# top.net
KiCad netlist of a schematic drawn in Altium Designer
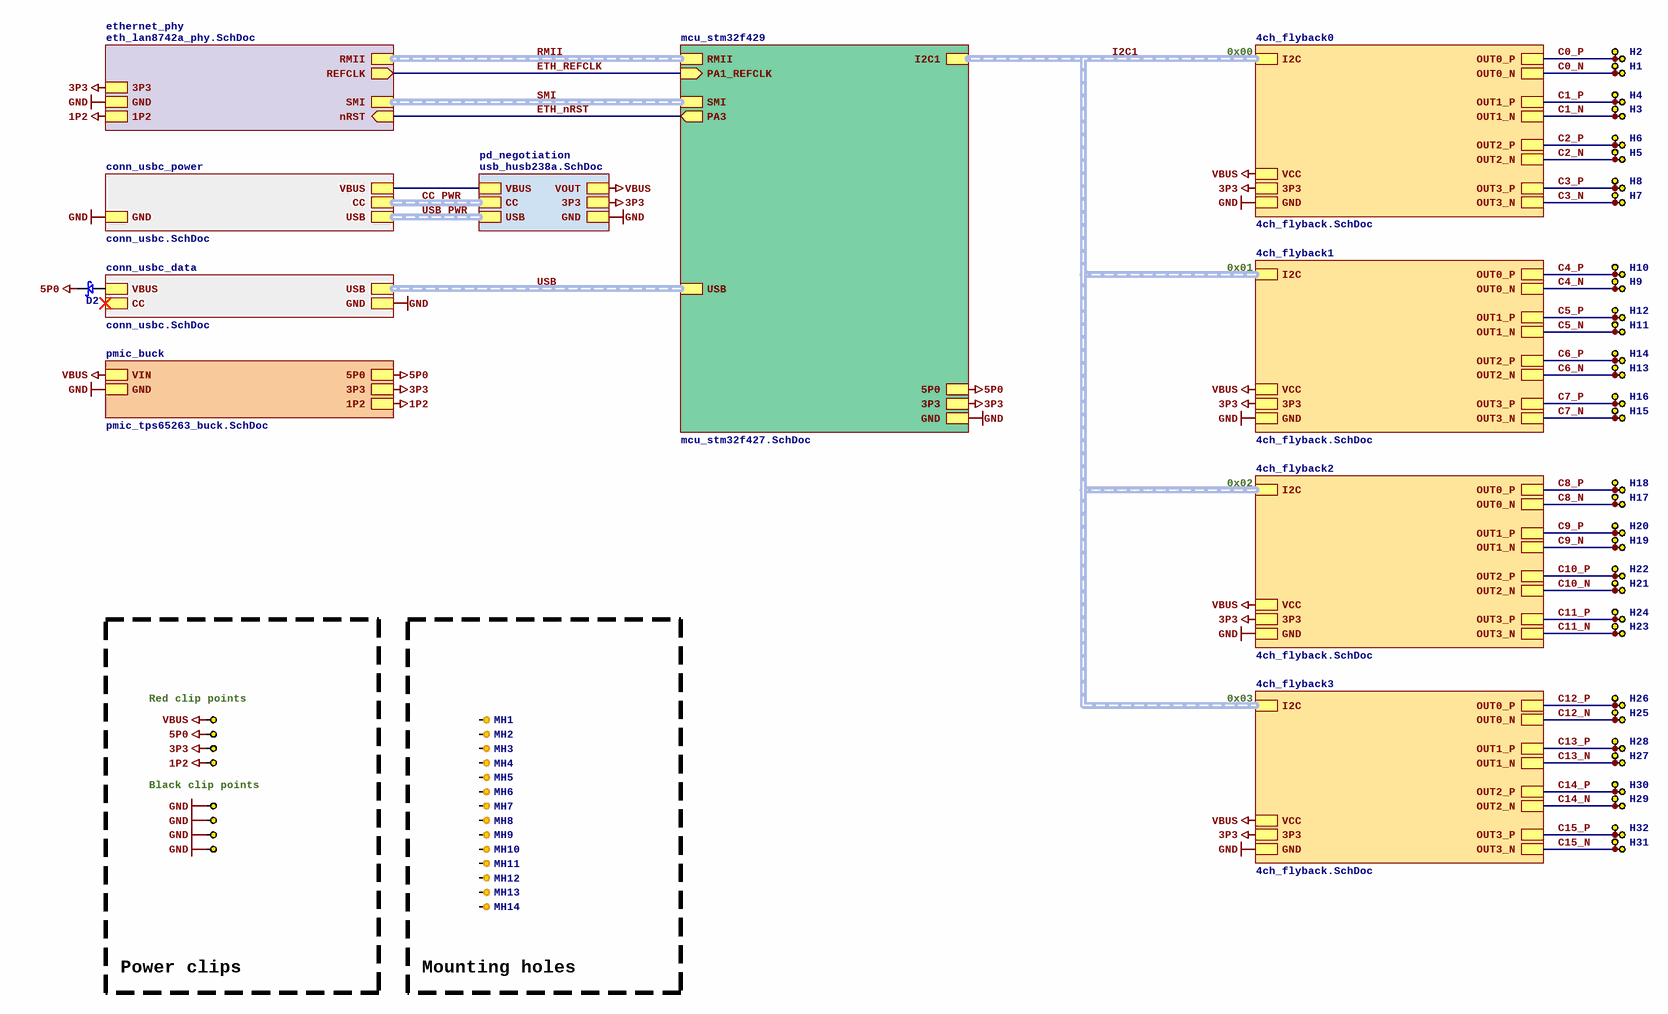
[diagram p0: top.SchDoc]

(export (version "E")
  (design (tool "Eeschema 10.0.6"))
  (components
    (comp (ref "D2")
      (value "B340A-13-F")
      (footprint "SMA")
      (description "Rectifier Diode, Schottky, 1 Phase, 1 Element, 3A, 40V V(RRM), Silicon")
      (fields (field (name "MANUFACTURER") "Diodes"))
      (libsource (lib "SSCP") (part "SCHOTTKY_B340A-13-F"))
    )
    (comp (ref "H1")
      (value "SMTSO-M2-10ET")
      (footprint "SMTSO-M2-10ET")
      (libsource (lib "SSCP") (part "STANDOFF_SMTSO-M2-10ET"))
    )
    (comp (ref "H2")
      (value "SMTSO-M2-10ET")
      (footprint "SMTSO-M2-10ET")
      (libsource (lib "SSCP") (part "STANDOFF_SMTSO-M2-10ET"))
    )
    (comp (ref "H3")
      (value "SMTSO-M2-10ET")
      (footprint "SMTSO-M2-10ET")
      (libsource (lib "SSCP") (part "STANDOFF_SMTSO-M2-10ET"))
    )
    (comp (ref "H4")
      (value "SMTSO-M2-10ET")
      (footprint "SMTSO-M2-10ET")
      (libsource (lib "SSCP") (part "STANDOFF_SMTSO-M2-10ET"))
    )
    (comp (ref "H5")
      (value "SMTSO-M2-10ET")
      (footprint "SMTSO-M2-10ET")
      (libsource (lib "SSCP") (part "STANDOFF_SMTSO-M2-10ET"))
    )
    (comp (ref "H6")
      (value "SMTSO-M2-10ET")
      (footprint "SMTSO-M2-10ET")
      (libsource (lib "SSCP") (part "STANDOFF_SMTSO-M2-10ET"))
    )
    (comp (ref "H7")
      (value "SMTSO-M2-10ET")
      (footprint "SMTSO-M2-10ET")
      (libsource (lib "SSCP") (part "STANDOFF_SMTSO-M2-10ET"))
    )
    (comp (ref "H8")
      (value "SMTSO-M2-10ET")
      (footprint "SMTSO-M2-10ET")
      (libsource (lib "SSCP") (part "STANDOFF_SMTSO-M2-10ET"))
    )
    (comp (ref "H9")
      (value "SMTSO-M2-10ET")
      (footprint "SMTSO-M2-10ET")
      (libsource (lib "SSCP") (part "STANDOFF_SMTSO-M2-10ET"))
    )
    (comp (ref "H10")
      (value "SMTSO-M2-10ET")
      (footprint "SMTSO-M2-10ET")
      (libsource (lib "SSCP") (part "STANDOFF_SMTSO-M2-10ET"))
    )
    (comp (ref "H11")
      (value "SMTSO-M2-10ET")
      (footprint "SMTSO-M2-10ET")
      (libsource (lib "SSCP") (part "STANDOFF_SMTSO-M2-10ET"))
    )
    (comp (ref "H12")
      (value "SMTSO-M2-10ET")
      (footprint "SMTSO-M2-10ET")
      (libsource (lib "SSCP") (part "STANDOFF_SMTSO-M2-10ET"))
    )
    (comp (ref "H13")
      (value "SMTSO-M2-10ET")
      (footprint "SMTSO-M2-10ET")
      (libsource (lib "SSCP") (part "STANDOFF_SMTSO-M2-10ET"))
    )
    (comp (ref "H14")
      (value "SMTSO-M2-10ET")
      (footprint "SMTSO-M2-10ET")
      (libsource (lib "SSCP") (part "STANDOFF_SMTSO-M2-10ET"))
    )
    (comp (ref "H15")
      (value "SMTSO-M2-10ET")
      (footprint "SMTSO-M2-10ET")
      (libsource (lib "SSCP") (part "STANDOFF_SMTSO-M2-10ET"))
    )
    (comp (ref "H16")
      (value "SMTSO-M2-10ET")
      (footprint "SMTSO-M2-10ET")
      (libsource (lib "SSCP") (part "STANDOFF_SMTSO-M2-10ET"))
    )
    (comp (ref "H17")
      (value "SMTSO-M2-10ET")
      (footprint "SMTSO-M2-10ET")
      (libsource (lib "SSCP") (part "STANDOFF_SMTSO-M2-10ET"))
    )
    (comp (ref "H18")
      (value "SMTSO-M2-10ET")
      (footprint "SMTSO-M2-10ET")
      (libsource (lib "SSCP") (part "STANDOFF_SMTSO-M2-10ET"))
    )
    (comp (ref "H19")
      (value "SMTSO-M2-10ET")
      (footprint "SMTSO-M2-10ET")
      (libsource (lib "SSCP") (part "STANDOFF_SMTSO-M2-10ET"))
    )
    (comp (ref "H20")
      (value "SMTSO-M2-10ET")
      (footprint "SMTSO-M2-10ET")
      (libsource (lib "SSCP") (part "STANDOFF_SMTSO-M2-10ET"))
    )
    (comp (ref "H21")
      (value "SMTSO-M2-10ET")
      (footprint "SMTSO-M2-10ET")
      (libsource (lib "SSCP") (part "STANDOFF_SMTSO-M2-10ET"))
    )
    (comp (ref "H22")
      (value "SMTSO-M2-10ET")
      (footprint "SMTSO-M2-10ET")
      (libsource (lib "SSCP") (part "STANDOFF_SMTSO-M2-10ET"))
    )
    (comp (ref "H23")
      (value "SMTSO-M2-10ET")
      (footprint "SMTSO-M2-10ET")
      (libsource (lib "SSCP") (part "STANDOFF_SMTSO-M2-10ET"))
    )
    (comp (ref "H24")
      (value "SMTSO-M2-10ET")
      (footprint "SMTSO-M2-10ET")
      (libsource (lib "SSCP") (part "STANDOFF_SMTSO-M2-10ET"))
    )
    (comp (ref "H25")
      (value "SMTSO-M2-10ET")
      (footprint "SMTSO-M2-10ET")
      (libsource (lib "SSCP") (part "STANDOFF_SMTSO-M2-10ET"))
    )
    (comp (ref "H26")
      (value "SMTSO-M2-10ET")
      (footprint "SMTSO-M2-10ET")
      (libsource (lib "SSCP") (part "STANDOFF_SMTSO-M2-10ET"))
    )
    (comp (ref "H27")
      (value "SMTSO-M2-10ET")
      (footprint "SMTSO-M2-10ET")
      (libsource (lib "SSCP") (part "STANDOFF_SMTSO-M2-10ET"))
    )
    (comp (ref "H28")
      (value "SMTSO-M2-10ET")
      (footprint "SMTSO-M2-10ET")
      (libsource (lib "SSCP") (part "STANDOFF_SMTSO-M2-10ET"))
    )
    (comp (ref "H29")
      (value "SMTSO-M2-10ET")
      (footprint "SMTSO-M2-10ET")
      (libsource (lib "SSCP") (part "STANDOFF_SMTSO-M2-10ET"))
    )
    (comp (ref "H30")
      (value "SMTSO-M2-10ET")
      (footprint "SMTSO-M2-10ET")
      (libsource (lib "SSCP") (part "STANDOFF_SMTSO-M2-10ET"))
    )
    (comp (ref "H31")
      (value "SMTSO-M2-10ET")
      (footprint "SMTSO-M2-10ET")
      (libsource (lib "SSCP") (part "STANDOFF_SMTSO-M2-10ET"))
    )
    (comp (ref "H32")
      (value "SMTSO-M2-10ET")
      (footprint "SMTSO-M2-10ET")
      (libsource (lib "SSCP") (part "STANDOFF_SMTSO-M2-10ET"))
    )
    (comp (ref "MH1") (value "HOLE") (footprint "HOLE_M3") (libsource (lib "miscellaneous") (part "HOLE")))
    (comp (ref "MH2") (value "HOLE") (footprint "HOLE_M3") (libsource (lib "miscellaneous") (part "HOLE")))
    (comp (ref "MH3") (value "HOLE") (footprint "HOLE_M3") (libsource (lib "miscellaneous") (part "HOLE")))
    (comp (ref "MH4") (value "HOLE") (footprint "HOLE_M3") (libsource (lib "miscellaneous") (part "HOLE")))
    (comp (ref "MH5") (value "HOLE") (footprint "HOLE_M3") (libsource (lib "miscellaneous") (part "HOLE")))
    (comp (ref "MH6") (value "HOLE") (footprint "HOLE_M3") (libsource (lib "miscellaneous") (part "HOLE")))
    (comp (ref "MH7") (value "HOLE") (footprint "HOLE_M3") (libsource (lib "miscellaneous") (part "HOLE")))
    (comp (ref "MH8") (value "HOLE") (footprint "HOLE_M3") (libsource (lib "miscellaneous") (part "HOLE")))
    (comp (ref "MH9") (value "HOLE") (footprint "HOLE_M3") (libsource (lib "miscellaneous") (part "HOLE")))
    (comp (ref "MH10") (value "HOLE") (footprint "HOLE_M3") (libsource (lib "miscellaneous") (part "HOLE")))
    (comp (ref "MH11") (value "HOLE") (footprint "HOLE_M3") (libsource (lib "miscellaneous") (part "HOLE")))
    (comp (ref "MH12") (value "HOLE") (footprint "HOLE_M3") (libsource (lib "miscellaneous") (part "HOLE")))
    (comp (ref "MH13") (value "HOLE") (footprint "HOLE_M3") (libsource (lib "miscellaneous") (part "HOLE")))
    (comp (ref "MH14") (value "HOLE") (footprint "HOLE_M3") (libsource (lib "miscellaneous") (part "HOLE")))
    (comp (ref "TP3")
      (value "RH-5000")
      (footprint "TP_RH-5000")
      (fields (field (name "MANUFACTURER") "ronghe"))
      (libsource (lib "database") (part "__template_testpoint"))
    )
    (comp (ref "TP4")
      (value "RH-5000")
      (footprint "TP_RH-5000")
      (fields (field (name "MANUFACTURER") "ronghe"))
      (libsource (lib "database") (part "__template_testpoint"))
    )
    (comp (ref "TP5")
      (value "RH-5001")
      (footprint "TP_RH-5001")
      (fields (field (name "MANUFACTURER") "ronghe"))
      (libsource (lib "database") (part "__template_testpoint"))
    )
    (comp (ref "TP6")
      (value "RH-5000")
      (footprint "TP_RH-5000")
      (fields (field (name "MANUFACTURER") "ronghe"))
      (libsource (lib "database") (part "__template_testpoint"))
    )
    (comp (ref "TP7")
      (value "RH-5001")
      (footprint "TP_RH-5001")
      (fields (field (name "MANUFACTURER") "ronghe"))
      (libsource (lib "database") (part "__template_testpoint"))
    )
    (comp (ref "TP8")
      (value "RH-5000")
      (footprint "TP_RH-5000")
      (fields (field (name "MANUFACTURER") "ronghe"))
      (libsource (lib "database") (part "__template_testpoint"))
    )
    (comp (ref "TP9")
      (value "RH-5001")
      (footprint "TP_RH-5001")
      (fields (field (name "MANUFACTURER") "ronghe"))
      (libsource (lib "database") (part "__template_testpoint"))
    )
    (comp (ref "TP10")
      (value "RH-5000")
      (footprint "TP_RH-5000")
      (fields (field (name "MANUFACTURER") "ronghe"))
      (libsource (lib "database") (part "__template_testpoint"))
    )
    (comp (ref "TP11")
      (value "RH-5001")
      (footprint "TP_RH-5001")
      (fields (field (name "MANUFACTURER") "ronghe"))
      (libsource (lib "database") (part "__template_testpoint"))
    )
    (comp (ref "TP12")
      (value "RH-5000")
      (footprint "TP_RH-5000")
      (fields (field (name "MANUFACTURER") "ronghe"))
      (libsource (lib "database") (part "__template_testpoint"))
    )
    (comp (ref "TP13")
      (value "RH-5001")
      (footprint "TP_RH-5001")
      (fields (field (name "MANUFACTURER") "ronghe"))
      (libsource (lib "database") (part "__template_testpoint"))
    )
    (comp (ref "TP14")
      (value "RH-5000")
      (footprint "TP_RH-5000")
      (fields (field (name "MANUFACTURER") "ronghe"))
      (libsource (lib "database") (part "__template_testpoint"))
    )
    (comp (ref "TP15")
      (value "RH-5001")
      (footprint "TP_RH-5001")
      (fields (field (name "MANUFACTURER") "ronghe"))
      (libsource (lib "database") (part "__template_testpoint"))
    )
    (comp (ref "TP16")
      (value "RH-5000")
      (footprint "TP_RH-5000")
      (fields (field (name "MANUFACTURER") "ronghe"))
      (libsource (lib "database") (part "__template_testpoint"))
    )
    (comp (ref "TP17")
      (value "RH-5001")
      (footprint "TP_RH-5001")
      (fields (field (name "MANUFACTURER") "ronghe"))
      (libsource (lib "database") (part "__template_testpoint"))
    )
    (comp (ref "TP18")
      (value "RH-5000")
      (footprint "TP_RH-5000")
      (fields (field (name "MANUFACTURER") "ronghe"))
      (libsource (lib "database") (part "__template_testpoint"))
    )
    (comp (ref "TP19")
      (value "RH-5001")
      (footprint "TP_RH-5001")
      (fields (field (name "MANUFACTURER") "ronghe"))
      (libsource (lib "database") (part "__template_testpoint"))
    )
    (comp (ref "TP20")
      (value "RH-5000")
      (footprint "TP_RH-5000")
      (fields (field (name "MANUFACTURER") "ronghe"))
      (libsource (lib "database") (part "__template_testpoint"))
    )
    (comp (ref "TP21")
      (value "RH-5001")
      (footprint "TP_RH-5001")
      (fields (field (name "MANUFACTURER") "ronghe"))
      (libsource (lib "database") (part "__template_testpoint"))
    )
    (comp (ref "TP22")
      (value "RH-5000")
      (footprint "TP_RH-5000")
      (fields (field (name "MANUFACTURER") "ronghe"))
      (libsource (lib "database") (part "__template_testpoint"))
    )
    (comp (ref "TP23")
      (value "RH-5001")
      (footprint "TP_RH-5001")
      (fields (field (name "MANUFACTURER") "ronghe"))
      (libsource (lib "database") (part "__template_testpoint"))
    )
    (comp (ref "TP24")
      (value "RH-5000")
      (footprint "TP_RH-5000")
      (fields (field (name "MANUFACTURER") "ronghe"))
      (libsource (lib "database") (part "__template_testpoint"))
    )
    (comp (ref "TP25")
      (value "RH-5001")
      (footprint "TP_RH-5001")
      (fields (field (name "MANUFACTURER") "ronghe"))
      (libsource (lib "database") (part "__template_testpoint"))
    )
    (comp (ref "TP26")
      (value "RH-5000")
      (footprint "TP_RH-5000")
      (fields (field (name "MANUFACTURER") "ronghe"))
      (libsource (lib "database") (part "__template_testpoint"))
    )
    (comp (ref "TP27")
      (value "RH-5001")
      (footprint "TP_RH-5001")
      (fields (field (name "MANUFACTURER") "ronghe"))
      (libsource (lib "database") (part "__template_testpoint"))
    )
    (comp (ref "TP28")
      (value "RH-5000")
      (footprint "TP_RH-5000")
      (fields (field (name "MANUFACTURER") "ronghe"))
      (libsource (lib "database") (part "__template_testpoint"))
    )
    (comp (ref "TP29")
      (value "RH-5001")
      (footprint "TP_RH-5001")
      (fields (field (name "MANUFACTURER") "ronghe"))
      (libsource (lib "database") (part "__template_testpoint"))
    )
    (comp (ref "TP30")
      (value "RH-5000")
      (footprint "TP_RH-5000")
      (fields (field (name "MANUFACTURER") "ronghe"))
      (libsource (lib "database") (part "__template_testpoint"))
    )
    (comp (ref "TP31")
      (value "RH-5001")
      (footprint "TP_RH-5001")
      (fields (field (name "MANUFACTURER") "ronghe"))
      (libsource (lib "database") (part "__template_testpoint"))
    )
    (comp (ref "TP32")
      (value "RH-5000")
      (footprint "TP_RH-5000")
      (fields (field (name "MANUFACTURER") "ronghe"))
      (libsource (lib "database") (part "__template_testpoint"))
    )
    (comp (ref "TP33")
      (value "RH-5000")
      (footprint "TP_RH-5000")
      (fields (field (name "MANUFACTURER") "ronghe"))
      (libsource (lib "database") (part "__template_testpoint"))
    )
    (comp (ref "TP34")
      (value "RH-5001")
      (footprint "TP_RH-5001")
      (fields (field (name "MANUFACTURER") "ronghe"))
      (libsource (lib "database") (part "__template_testpoint"))
    )
    (comp (ref "TP35")
      (value "RH-5000")
      (footprint "TP_RH-5000")
      (fields (field (name "MANUFACTURER") "ronghe"))
      (libsource (lib "database") (part "__template_testpoint"))
    )
    (comp (ref "TP36")
      (value "RH-5000")
      (footprint "TP_RH-5000")
      (fields (field (name "MANUFACTURER") "ronghe"))
      (libsource (lib "database") (part "__template_testpoint"))
    )
    (comp (ref "TP37")
      (value "RH-5000")
      (footprint "TP_RH-5000")
      (fields (field (name "MANUFACTURER") "ronghe"))
      (libsource (lib "database") (part "__template_testpoint"))
    )
    (comp (ref "TP38")
      (value "RH-5001")
      (footprint "TP_RH-5001")
      (fields (field (name "MANUFACTURER") "ronghe"))
      (libsource (lib "database") (part "__template_testpoint"))
    )
    (comp (ref "TP39")
      (value "RH-5001")
      (footprint "TP_RH-5001")
      (fields (field (name "MANUFACTURER") "ronghe"))
      (libsource (lib "database") (part "__template_testpoint"))
    )
    (comp (ref "TP41")
      (value "RH-5001")
      (footprint "TP_RH-5001")
      (fields (field (name "MANUFACTURER") "ronghe"))
      (libsource (lib "database") (part "__template_testpoint"))
    )
    (comp (ref "TP43")
      (value "RH-5001")
      (footprint "TP_RH-5001")
      (fields (field (name "MANUFACTURER") "ronghe"))
      (libsource (lib "database") (part "__template_testpoint"))
    )
    (comp (ref "TP45")
      (value "RH-5001")
      (footprint "TP_RH-5001")
      (fields (field (name "MANUFACTURER") "ronghe"))
      (libsource (lib "database") (part "__template_testpoint"))
    )
  )
  (nets
    (net (code "7") (name "/C0_N") (class "Default")
      (node (ref "H1") (pin "1") (pintype "passive"))
      (node (ref "TP5") (pin "1") (pintype "passive"))
    )
    (net (code "8") (name "/C0_P") (class "Default")
      (node (ref "H2") (pin "1") (pintype "passive"))
      (node (ref "TP4") (pin "1") (pintype "passive"))
    )
    (net (code "9") (name "/C1_N") (class "Default")
      (node (ref "H3") (pin "1") (pintype "passive"))
      (node (ref "TP7") (pin "1") (pintype "passive"))
    )
    (net (code "10") (name "/C1_P") (class "Default")
      (node (ref "H4") (pin "1") (pintype "passive"))
      (node (ref "TP6") (pin "1") (pintype "passive"))
    )
    (net (code "11") (name "/C2_N") (class "Default")
      (node (ref "H5") (pin "1") (pintype "passive"))
      (node (ref "TP9") (pin "1") (pintype "passive"))
    )
    (net (code "12") (name "/C2_P") (class "Default")
      (node (ref "H6") (pin "1") (pintype "passive"))
      (node (ref "TP8") (pin "1") (pintype "passive"))
    )
    (net (code "13") (name "/C3_N") (class "Default")
      (node (ref "H7") (pin "1") (pintype "passive"))
      (node (ref "TP11") (pin "1") (pintype "passive"))
    )
    (net (code "14") (name "/C3_P") (class "Default")
      (node (ref "H8") (pin "1") (pintype "passive"))
      (node (ref "TP10") (pin "1") (pintype "passive"))
    )
    (net (code "15") (name "/C4_N") (class "Default")
      (node (ref "H9") (pin "1") (pintype "passive"))
      (node (ref "TP13") (pin "1") (pintype "passive"))
    )
    (net (code "16") (name "/C4_P") (class "Default")
      (node (ref "H10") (pin "1") (pintype "passive"))
      (node (ref "TP12") (pin "1") (pintype "passive"))
    )
    (net (code "17") (name "/C5_N") (class "Default")
      (node (ref "H11") (pin "1") (pintype "passive"))
      (node (ref "TP15") (pin "1") (pintype "passive"))
    )
    (net (code "18") (name "/C5_P") (class "Default")
      (node (ref "H12") (pin "1") (pintype "passive"))
      (node (ref "TP14") (pin "1") (pintype "passive"))
    )
    (net (code "19") (name "/C6_N") (class "Default")
      (node (ref "H13") (pin "1") (pintype "passive"))
      (node (ref "TP17") (pin "1") (pintype "passive"))
    )
    (net (code "20") (name "/C6_P") (class "Default")
      (node (ref "H14") (pin "1") (pintype "passive"))
      (node (ref "TP16") (pin "1") (pintype "passive"))
    )
    (net (code "21") (name "/C7_N") (class "Default")
      (node (ref "H15") (pin "1") (pintype "passive"))
      (node (ref "TP19") (pin "1") (pintype "passive"))
    )
    (net (code "22") (name "/C7_P") (class "Default")
      (node (ref "H16") (pin "1") (pintype "passive"))
      (node (ref "TP18") (pin "1") (pintype "passive"))
    )
    (net (code "23") (name "/C8_N") (class "Default")
      (node (ref "H17") (pin "1") (pintype "passive"))
      (node (ref "TP21") (pin "1") (pintype "passive"))
    )
    (net (code "24") (name "/C8_P") (class "Default")
      (node (ref "H18") (pin "1") (pintype "passive"))
      (node (ref "TP20") (pin "1") (pintype "passive"))
    )
    (net (code "25") (name "/C9_N") (class "Default")
      (node (ref "H19") (pin "1") (pintype "passive"))
      (node (ref "TP23") (pin "1") (pintype "passive"))
    )
    (net (code "26") (name "/C9_P") (class "Default")
      (node (ref "H20") (pin "1") (pintype "passive"))
      (node (ref "TP22") (pin "1") (pintype "passive"))
    )
    (net (code "27") (name "/C10_N") (class "Default")
      (node (ref "H21") (pin "1") (pintype "passive"))
      (node (ref "TP25") (pin "1") (pintype "passive"))
    )
    (net (code "28") (name "/C10_P") (class "Default")
      (node (ref "H22") (pin "1") (pintype "passive"))
      (node (ref "TP24") (pin "1") (pintype "passive"))
    )
    (net (code "29") (name "/C11_N") (class "Default")
      (node (ref "H23") (pin "1") (pintype "passive"))
      (node (ref "TP27") (pin "1") (pintype "passive"))
    )
    (net (code "30") (name "/C11_P") (class "Default")
      (node (ref "H24") (pin "1") (pintype "passive"))
      (node (ref "TP26") (pin "1") (pintype "passive"))
    )
    (net (code "31") (name "/C12_N") (class "Default")
      (node (ref "H25") (pin "1") (pintype "passive"))
      (node (ref "TP29") (pin "1") (pintype "passive"))
    )
    (net (code "32") (name "/C12_P") (class "Default")
      (node (ref "H26") (pin "1") (pintype "passive"))
      (node (ref "TP28") (pin "1") (pintype "passive"))
    )
    (net (code "33") (name "/C13_N") (class "Default")
      (node (ref "H27") (pin "1") (pintype "passive"))
      (node (ref "TP31") (pin "1") (pintype "passive"))
    )
    (net (code "34") (name "/C13_P") (class "Default")
      (node (ref "H28") (pin "1") (pintype "passive"))
      (node (ref "TP30") (pin "1") (pintype "passive"))
    )
    (net (code "35") (name "/C14_N") (class "Default")
      (node (ref "H29") (pin "1") (pintype "passive"))
      (node (ref "TP34") (pin "1") (pintype "passive"))
    )
    (net (code "36") (name "/C14_P") (class "Default")
      (node (ref "H30") (pin "1") (pintype "passive"))
      (node (ref "TP32") (pin "1") (pintype "passive"))
    )
    (net (code "37") (name "/C15_N") (class "Default")
      (node (ref "H31") (pin "1") (pintype "passive"))
      (node (ref "TP38") (pin "1") (pintype "passive"))
    )
    (net (code "38") (name "/C15_P") (class "Default")
      (node (ref "H32") (pin "1") (pintype "passive"))
      (node (ref "TP36") (pin "1") (pintype "passive"))
    )
    (net (code "43") (name "/VBUS_1") (class "Default") (node (ref "D2") (pin "1") (pintype "passive")))
    (net (code "50") (name "1P2") (class "Default") (node (ref "TP37") (pin "1") (pintype "passive")))
    (net (code "51") (name "3P3") (class "Default") (node (ref "TP35") (pin "1") (pintype "passive")))
    (net (code "52") (name "5P0") (class "Default")
      (node (ref "D2") (pin "2") (pintype "passive"))
      (node (ref "TP33") (pin "1") (pintype "passive"))
    )
    (net (code "53") (name "GND") (class "Default")
      (node (ref "TP39") (pin "1") (pintype "passive"))
      (node (ref "TP41") (pin "1") (pintype "passive"))
      (node (ref "TP43") (pin "1") (pintype "passive"))
      (node (ref "TP45") (pin "1") (pintype "passive"))
    )
    (net (code "54") (name "VBUS") (class "Default") (node (ref "TP3") (pin "1") (pintype "passive")))
    (net (code "55") (name "unconnected-(MH1-Pad1)") (class "Default")
      (node (ref "MH1") (pin "1") (pintype "passive"))
    )
    (net (code "56") (name "unconnected-(MH2-Pad1)") (class "Default")
      (node (ref "MH2") (pin "1") (pintype "passive"))
    )
    (net (code "57") (name "unconnected-(MH3-Pad1)") (class "Default")
      (node (ref "MH3") (pin "1") (pintype "passive"))
    )
    (net (code "58") (name "unconnected-(MH4-Pad1)") (class "Default")
      (node (ref "MH4") (pin "1") (pintype "passive"))
    )
    (net (code "59") (name "unconnected-(MH5-Pad1)") (class "Default")
      (node (ref "MH5") (pin "1") (pintype "passive"))
    )
    (net (code "60") (name "unconnected-(MH6-Pad1)") (class "Default")
      (node (ref "MH6") (pin "1") (pintype "passive"))
    )
    (net (code "61") (name "unconnected-(MH7-Pad1)") (class "Default")
      (node (ref "MH7") (pin "1") (pintype "passive"))
    )
    (net (code "62") (name "unconnected-(MH8-Pad1)") (class "Default")
      (node (ref "MH8") (pin "1") (pintype "passive"))
    )
    (net (code "63") (name "unconnected-(MH9-Pad1)") (class "Default")
      (node (ref "MH9") (pin "1") (pintype "passive"))
    )
    (net (code "64") (name "unconnected-(MH10-Pad1)") (class "Default")
      (node (ref "MH10") (pin "1") (pintype "passive"))
    )
    (net (code "65") (name "unconnected-(MH11-Pad1)") (class "Default")
      (node (ref "MH11") (pin "1") (pintype "passive"))
    )
    (net (code "66") (name "unconnected-(MH12-Pad1)") (class "Default")
      (node (ref "MH12") (pin "1") (pintype "passive"))
    )
    (net (code "67") (name "unconnected-(MH13-Pad1)") (class "Default")
      (node (ref "MH13") (pin "1") (pintype "passive"))
    )
    (net (code "68") (name "unconnected-(MH14-Pad1)") (class "Default")
      (node (ref "MH14") (pin "1") (pintype "passive"))
    )
  )
)
